# mmimplant.net
KiCad netlist of a schematic drawn in EAGLE
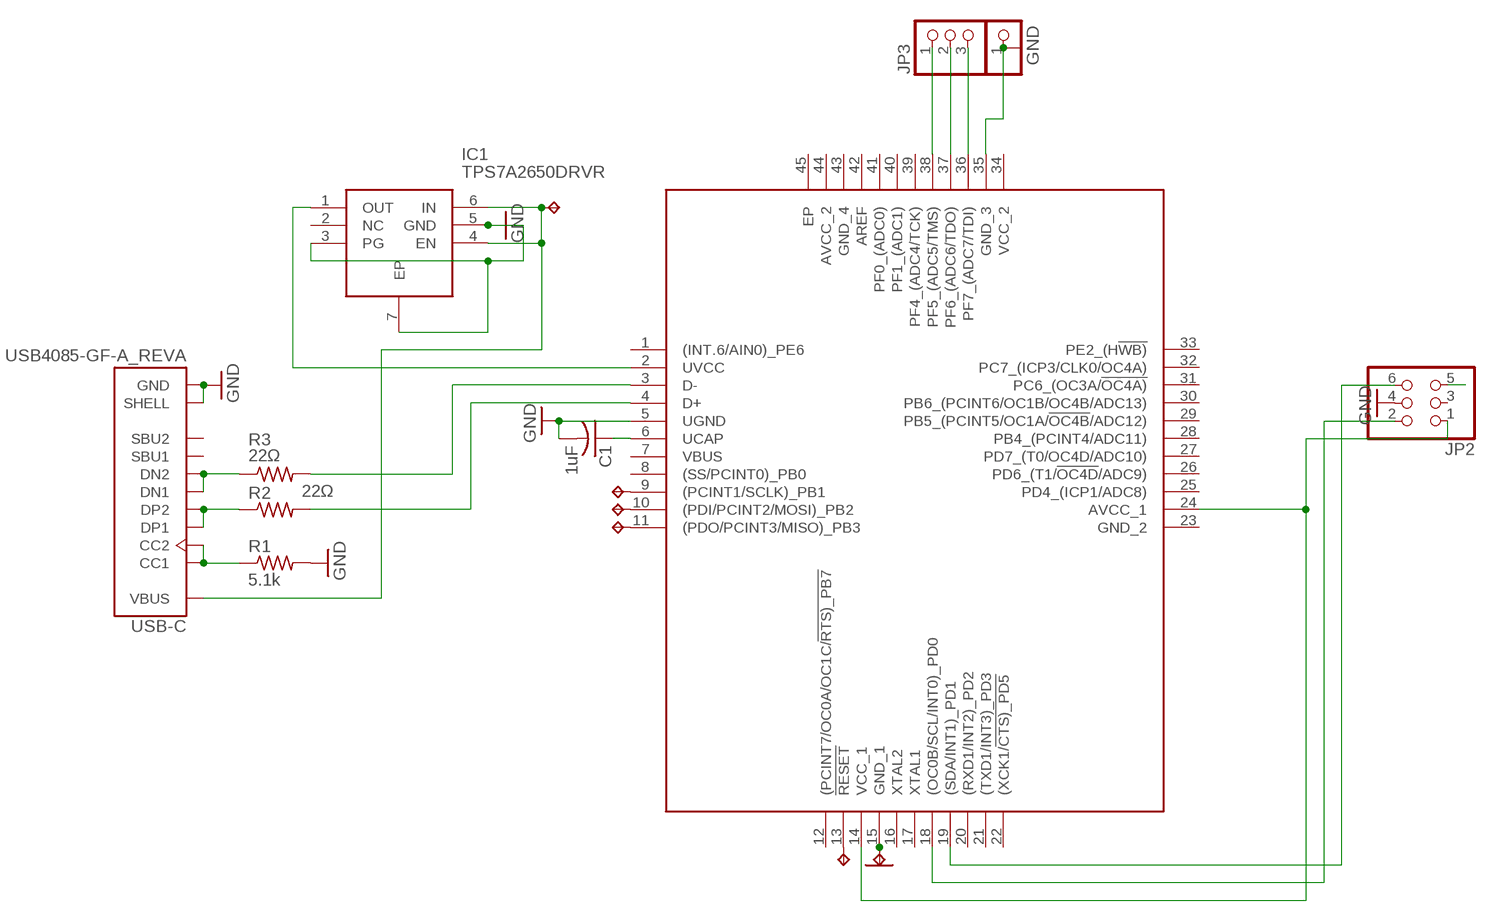
[diagram p0: schematic, sheet 1]

(export (version "E")
  (design (tool "Eeschema 10.0.6"))
  (components
    (comp (ref "5V")
      (value "TPTP17R")
      (footprint "eagle-import:TP17R")
      (libsource (lib "eagle-import") (part "TPTP17R"))
    )
    (comp (ref "C1")
      (value "1uF")
      (footprint "eagle-import:C0805")
      (libsource (lib "eagle-import") (part "C-USC0805"))
    )
    (comp (ref "GND")
      (value "TPTP17R")
      (footprint "eagle-import:TP17R")
      (libsource (lib "eagle-import") (part "TPTP17R"))
    )
    (comp (ref "IC1")
      (value "TPS7A2650DRVR")
      (footprint "eagle-import:SON65P200X200X80-7N")
      (fields (field (name "MOUSER_PART_NUMBER") "595-TPS7A2650DRVR"))
      (libsource (lib "eagle-import") (part "TPS7A2650DRVR"))
    )
    (comp (ref "IC2")
      (value "ATMEGA32U4-MU")
      (footprint "eagle-import:QFN50P700X700X100-45N")
      (fields (field (name "MOUSER_PART_NUMBER") "556-ATMEGA32U4-MU"))
      (libsource (lib "eagle-import") (part "ATMEGA32U4-MU"))
    )
    (comp (ref "JP1")
      (value "PINHD-1X1")
      (footprint "eagle-import:1X01")
      (libsource (lib "eagle-import") (part "PINHD-1X1"))
    )
    (comp (ref "JP2")
      (value "PINHD-2X3")
      (footprint "eagle-import:2X03")
      (libsource (lib "eagle-import") (part "PINHD-2X3"))
    )
    (comp (ref "JP3")
      (value "PINHD-1X3")
      (footprint "eagle-import:1X03")
      (libsource (lib "eagle-import") (part "PINHD-1X3"))
    )
    (comp (ref "MISO")
      (value "TPTP17R")
      (footprint "eagle-import:TP17R")
      (libsource (lib "eagle-import") (part "TPTP17R"))
    )
    (comp (ref "MOSI")
      (value "TPTP17R")
      (footprint "eagle-import:TP17R")
      (libsource (lib "eagle-import") (part "TPTP17R"))
    )
    (comp (ref "R1")
      (value "5.1k")
      (footprint "eagle-import:R0603")
      (libsource (lib "eagle-import") (part "R-US_R0603"))
    )
    (comp (ref "R2")
      (value "22Ω")
      (footprint "eagle-import:R0805")
      (libsource (lib "eagle-import") (part "R-US_R0805"))
    )
    (comp (ref "R3")
      (value "22Ω")
      (footprint "eagle-import:R0805")
      (libsource (lib "eagle-import") (part "R-US_R0805"))
    )
    (comp (ref "RST")
      (value "TPTP17R")
      (footprint "eagle-import:TP17R")
      (libsource (lib "eagle-import") (part "TPTP17R"))
    )
    (comp (ref "SCLK")
      (value "TPTP17R")
      (footprint "eagle-import:TP17R")
      (libsource (lib "eagle-import") (part "TPTP17R"))
    )
    (comp (ref "USB-C")
      (value "USB4085-GF-A_REVA")
      (footprint "eagle-import:GCT_USB4085-GF-A_REVA")
      (fields (field (name "MF") "Global Connector Technology") (field (name "MP") "USB4085-GF-A"))
      (libsource (lib "eagle-import") (part "USB4085-GF-A_REVA"))
    )
  )
  (nets
    (net (code "1") (name "GND") (class "Default")
      (node (ref "C1") (pin "2") (pinfunction "2_2") (pintype "passive"))
      (node (ref "GND") (pin "TP") (pinfunction "TP_TP") (pintype "input"))
      (node (ref "IC1") (pin "3") (pinfunction "PG_3") (pintype "bidirectional"))
      (node (ref "IC1") (pin "5") (pinfunction "GND_5") (pintype "bidirectional"))
      (node (ref "IC1") (pin "7") (pinfunction "EP_7") (pintype "bidirectional"))
      (node (ref "IC2") (pin "15") (pinfunction "GND_1_15") (pintype "bidirectional"))
      (node (ref "IC2") (pin "35") (pinfunction "GND_3_35") (pintype "bidirectional"))
      (node (ref "IC2") (pin "5") (pinfunction "UGND_5") (pintype "bidirectional"))
      (node (ref "JP1") (pin "1") (pinfunction "1_1") (pintype "passive"))
      (node (ref "JP2") (pin "4") (pinfunction "4_4") (pintype "passive"))
      (node (ref "R1") (pin "2") (pinfunction "2_2") (pintype "passive"))
      (node (ref "USB-C") (pin "A1") (pinfunction "GND_A1") (pintype "passive"))
      (node (ref "USB-C") (pin "A12") (pinfunction "GND_A12") (pintype "passive"))
      (node (ref "USB-C") (pin "B1") (pinfunction "GND_B1") (pintype "passive"))
      (node (ref "USB-C") (pin "B12") (pinfunction "GND_B12") (pintype "passive"))
      (node (ref "USB-C") (pin "P1") (pinfunction "SHELL_P1") (pintype "passive"))
      (node (ref "USB-C") (pin "P2") (pinfunction "SHELL_P2") (pintype "passive"))
      (node (ref "USB-C") (pin "P3") (pinfunction "SHELL_P3") (pintype "passive"))
      (node (ref "USB-C") (pin "P4") (pinfunction "SHELL_P4") (pintype "passive"))
    )
    (net (code "2") (name "Net-(IC1-EN)") (class "Default")
      (node (ref "5V") (pin "TP") (pinfunction "TP_TP") (pintype "input"))
      (node (ref "IC1") (pin "4") (pinfunction "EN_4") (pintype "bidirectional"))
      (node (ref "IC1") (pin "6") (pinfunction "IN_6") (pintype "bidirectional"))
      (node (ref "USB-C") (pin "A4") (pinfunction "VBUS_A4") (pintype "power_in"))
      (node (ref "USB-C") (pin "A9") (pinfunction "VBUS_A9") (pintype "power_in"))
      (node (ref "USB-C") (pin "B4") (pinfunction "VBUS_B4") (pintype "power_in"))
      (node (ref "USB-C") (pin "B9") (pinfunction "VBUS_B9") (pintype "power_in"))
    )
    (net (code "3") (name "Net-(IC1-OUT)") (class "Default")
      (node (ref "IC1") (pin "1") (pinfunction "OUT_1") (pintype "bidirectional"))
      (node (ref "IC2") (pin "2") (pinfunction "UVCC_2") (pintype "bidirectional"))
    )
    (net (code "4") (name "Net-(IC2-(OC0B{slash}SCL{slash}INT0)_PD0)") (class "Default")
      (node (ref "IC2") (pin "18") (pinfunction "(OC0B/SCL/INT0)_PD0_18") (pintype "bidirectional"))
      (node (ref "JP2") (pin "2") (pinfunction "2_2") (pintype "passive"))
    )
    (net (code "5") (name "Net-(IC2-(PCINT1{slash}SCLK)_PB1)") (class "Default")
      (node (ref "IC2") (pin "9") (pinfunction "(PCINT1/SCLK)_PB1_9") (pintype "bidirectional"))
      (node (ref "SCLK") (pin "TP") (pinfunction "TP_TP") (pintype "input"))
    )
    (net (code "6") (name "Net-(IC2-(PDI{slash}PCINT2{slash}MOSI)_PB2)") (class "Default")
      (node (ref "IC2") (pin "10") (pinfunction "(PDI/PCINT2/MOSI)_PB2_10") (pintype "bidirectional"))
      (node (ref "MOSI") (pin "TP") (pinfunction "TP_TP") (pintype "input"))
    )
    (net (code "7") (name "Net-(IC2-(PDO{slash}PCINT3{slash}MISO)_PB3)") (class "Default")
      (node (ref "IC2") (pin "11") (pinfunction "(PDO/PCINT3/MISO)_PB3_11") (pintype "bidirectional"))
      (node (ref "MISO") (pin "TP") (pinfunction "TP_TP") (pintype "input"))
    )
    (net (code "8") (name "Net-(IC2-(SDA{slash}INT1)_PD1)") (class "Default")
      (node (ref "IC2") (pin "19") (pinfunction "(SDA/INT1)_PD1_19") (pintype "bidirectional"))
      (node (ref "JP2") (pin "6") (pinfunction "6_6") (pintype "passive"))
    )
    (net (code "9") (name "Net-(IC2-AVCC_1)") (class "Default")
      (node (ref "IC2") (pin "14") (pinfunction "VCC_1_14") (pintype "bidirectional"))
      (node (ref "IC2") (pin "24") (pinfunction "AVCC_1_24") (pintype "bidirectional"))
      (node (ref "JP2") (pin "1") (pinfunction "1_1") (pintype "passive"))
    )
    (net (code "10") (name "Net-(IC2-D+)") (class "Default")
      (node (ref "IC2") (pin "4") (pinfunction "D+_4") (pintype "bidirectional"))
      (node (ref "R2") (pin "2") (pinfunction "2_2") (pintype "passive"))
    )
    (net (code "11") (name "Net-(IC2-D-)") (class "Default")
      (node (ref "IC2") (pin "3") (pinfunction "D-_3") (pintype "bidirectional"))
      (node (ref "R3") (pin "2") (pinfunction "2_2") (pintype "passive"))
    )
    (net (code "12") (name "Net-(IC2-PF5_(ADC5{slash}TMS))") (class "Default")
      (node (ref "IC2") (pin "38") (pinfunction "PF5_(ADC5/TMS)_38") (pintype "bidirectional"))
      (node (ref "JP3") (pin "1") (pinfunction "1_1") (pintype "passive"))
    )
    (net (code "13") (name "Net-(IC2-PF6_(ADC6{slash}TDO))") (class "Default")
      (node (ref "IC2") (pin "37") (pinfunction "PF6_(ADC6/TDO)_37") (pintype "bidirectional"))
      (node (ref "JP3") (pin "2") (pinfunction "2_2") (pintype "passive"))
    )
    (net (code "14") (name "Net-(IC2-PF7_(ADC7{slash}TDI))") (class "Default")
      (node (ref "IC2") (pin "36") (pinfunction "PF7_(ADC7/TDI)_36") (pintype "bidirectional"))
      (node (ref "JP3") (pin "3") (pinfunction "3_3") (pintype "passive"))
    )
    (net (code "15") (name "Net-(IC2-UCAP)") (class "Default")
      (node (ref "C1") (pin "1") (pinfunction "1_1") (pintype "passive"))
      (node (ref "IC2") (pin "6") (pinfunction "UCAP_6") (pintype "bidirectional"))
    )
    (net (code "16") (name "Net-(IC2-~{RESET})") (class "Default")
      (node (ref "IC2") (pin "13") (pinfunction "~{RESET}_13") (pintype "bidirectional"))
      (node (ref "RST") (pin "TP") (pinfunction "TP_TP") (pintype "input"))
    )
    (net (code "17") (name "Net-(USB-C-CC1)") (class "Default")
      (node (ref "R1") (pin "1") (pinfunction "1_1") (pintype "passive"))
      (node (ref "USB-C") (pin "A5") (pinfunction "CC1_A5") (pintype "bidirectional"))
      (node (ref "USB-C") (pin "B5") (pinfunction "CC2_B5") (pintype "bidirectional"))
    )
    (net (code "18") (name "Net-(USB-C-DN1)") (class "Default")
      (node (ref "R3") (pin "1") (pinfunction "1_1") (pintype "passive"))
      (node (ref "USB-C") (pin "A7") (pinfunction "DN1_A7") (pintype "bidirectional"))
      (node (ref "USB-C") (pin "B7") (pinfunction "DN2_B7") (pintype "bidirectional"))
    )
    (net (code "19") (name "Net-(USB-C-DP1)") (class "Default")
      (node (ref "R2") (pin "1") (pinfunction "1_1") (pintype "passive"))
      (node (ref "USB-C") (pin "A6") (pinfunction "DP1_A6") (pintype "bidirectional"))
      (node (ref "USB-C") (pin "B6") (pinfunction "DP2_B6") (pintype "bidirectional"))
    )
    (net (code "20") (name "unconnected-(IC1-NC-Pad2)") (class "Default")
      (node (ref "IC1") (pin "2") (pinfunction "NC_2") (pintype "no_connect"))
    )
    (net (code "21") (name "unconnected-(IC2-(INT.6{slash}AIN0)_PE6-Pad1)") (class "Default")
      (node (ref "IC2") (pin "1") (pinfunction "(INT.6/AIN0)_PE6_1") (pintype "bidirectional"))
    )
    (net (code "22") (name "unconnected-(IC2-(PCINT7{slash}OC0A{slash}OC1C{slash}~{RTS})_PB7-Pad12)") (class "Default")
      (node (ref "IC2") (pin "12") (pinfunction "(PCINT7/OC0A/OC1C/~{RTS})_PB7_12") (pintype "bidirectional"))
    )
    (net (code "23") (name "unconnected-(IC2-(RXD1{slash}INT2)_PD2-Pad20)") (class "Default")
      (node (ref "IC2") (pin "20") (pinfunction "(RXD1/INT2)_PD2_20") (pintype "bidirectional"))
    )
    (net (code "24") (name "unconnected-(IC2-(SS{slash}PCINT0)_PB0-Pad8)") (class "Default")
      (node (ref "IC2") (pin "8") (pinfunction "(SS/PCINT0)_PB0_8") (pintype "bidirectional"))
    )
    (net (code "25") (name "unconnected-(IC2-(TXD1{slash}INT3)_PD3-Pad21)") (class "Default")
      (node (ref "IC2") (pin "21") (pinfunction "(TXD1/INT3)_PD3_21") (pintype "bidirectional"))
    )
    (net (code "26") (name "unconnected-(IC2-(XCK1{slash}~{CTS})_PD5-Pad22)") (class "Default")
      (node (ref "IC2") (pin "22") (pinfunction "(XCK1/~{CTS})_PD5_22") (pintype "bidirectional"))
    )
    (net (code "27") (name "unconnected-(IC2-AREF-Pad42)") (class "Default")
      (node (ref "IC2") (pin "42") (pinfunction "AREF_42") (pintype "bidirectional"))
    )
    (net (code "28") (name "unconnected-(IC2-AVCC_2-Pad44)") (class "Default")
      (node (ref "IC2") (pin "44") (pinfunction "AVCC_2_44") (pintype "bidirectional"))
    )
    (net (code "29") (name "unconnected-(IC2-EP-Pad45)") (class "Default")
      (node (ref "IC2") (pin "45") (pinfunction "EP_45") (pintype "bidirectional"))
    )
    (net (code "30") (name "unconnected-(IC2-GND_2-Pad23)") (class "Default")
      (node (ref "IC2") (pin "23") (pinfunction "GND_2_23") (pintype "bidirectional"))
    )
    (net (code "31") (name "unconnected-(IC2-GND_4-Pad43)") (class "Default")
      (node (ref "IC2") (pin "43") (pinfunction "GND_4_43") (pintype "bidirectional"))
    )
    (net (code "32") (name "unconnected-(IC2-PB4_(PCINT4{slash}ADC11)-Pad28)") (class "Default")
      (node (ref "IC2") (pin "28") (pinfunction "PB4_(PCINT4/ADC11)_28") (pintype "bidirectional"))
    )
    (net (code "33") (name "unconnected-(IC2-PB5_(PCINT5{slash}OC1A{slash}~{OC4B}{slash}ADC12)-Pad29)") (class "Default")
      (node (ref "IC2") (pin "29") (pinfunction "PB5_(PCINT5/OC1A/~{OC4B}/ADC12)_29") (pintype "bidirectional"))
    )
    (net (code "34") (name "unconnected-(IC2-PB6_(PCINT6{slash}OC1B{slash}OC4B{slash}ADC13)-Pad30)") (class "Default")
      (node (ref "IC2") (pin "30") (pinfunction "PB6_(PCINT6/OC1B/OC4B/ADC13)_30") (pintype "bidirectional"))
    )
    (net (code "35") (name "unconnected-(IC2-PC6_(OC3A{slash}~{OC4A})-Pad31)") (class "Default")
      (node (ref "IC2") (pin "31") (pinfunction "PC6_(OC3A/~{OC4A})_31") (pintype "bidirectional"))
    )
    (net (code "36") (name "unconnected-(IC2-PC7_(ICP3{slash}CLK0{slash}OC4A)-Pad32)") (class "Default")
      (node (ref "IC2") (pin "32") (pinfunction "PC7_(ICP3/CLK0/OC4A)_32") (pintype "bidirectional"))
    )
    (net (code "37") (name "unconnected-(IC2-PD4_(ICP1{slash}ADC8)-Pad25)") (class "Default")
      (node (ref "IC2") (pin "25") (pinfunction "PD4_(ICP1/ADC8)_25") (pintype "bidirectional"))
    )
    (net (code "38") (name "unconnected-(IC2-PD6_(T1{slash}~{OC4D}{slash}ADC9)-Pad26)") (class "Default")
      (node (ref "IC2") (pin "26") (pinfunction "PD6_(T1/~{OC4D}/ADC9)_26") (pintype "bidirectional"))
    )
    (net (code "39") (name "unconnected-(IC2-PD7_(T0{slash}OC4D{slash}ADC10)-Pad27)") (class "Default")
      (node (ref "IC2") (pin "27") (pinfunction "PD7_(T0/OC4D/ADC10)_27") (pintype "bidirectional"))
    )
    (net (code "40") (name "unconnected-(IC2-PE2_(H~{WB})-Pad33)") (class "Default")
      (node (ref "IC2") (pin "33") (pinfunction "PE2_(H~{WB})_33") (pintype "bidirectional"))
    )
    (net (code "41") (name "unconnected-(IC2-PF0_(ADC0)-Pad41)") (class "Default")
      (node (ref "IC2") (pin "41") (pinfunction "PF0_(ADC0)_41") (pintype "bidirectional"))
    )
    (net (code "42") (name "unconnected-(IC2-PF1_(ADC1)-Pad40)") (class "Default")
      (node (ref "IC2") (pin "40") (pinfunction "PF1_(ADC1)_40") (pintype "bidirectional"))
    )
    (net (code "43") (name "unconnected-(IC2-PF4_(ADC4{slash}TCK)-Pad39)") (class "Default")
      (node (ref "IC2") (pin "39") (pinfunction "PF4_(ADC4/TCK)_39") (pintype "bidirectional"))
    )
    (net (code "44") (name "unconnected-(IC2-VBUS-Pad7)") (class "Default")
      (node (ref "IC2") (pin "7") (pinfunction "VBUS_7") (pintype "bidirectional"))
    )
    (net (code "45") (name "unconnected-(IC2-VCC_2-Pad34)") (class "Default")
      (node (ref "IC2") (pin "34") (pinfunction "VCC_2_34") (pintype "bidirectional"))
    )
    (net (code "46") (name "unconnected-(IC2-XTAL1-Pad17)") (class "Default")
      (node (ref "IC2") (pin "17") (pinfunction "XTAL1_17") (pintype "bidirectional"))
    )
    (net (code "47") (name "unconnected-(IC2-XTAL2-Pad16)") (class "Default")
      (node (ref "IC2") (pin "16") (pinfunction "XTAL2_16") (pintype "bidirectional"))
    )
    (net (code "48") (name "unconnected-(JP2-Pad3)") (class "Default")
      (node (ref "JP2") (pin "3") (pinfunction "3_3") (pintype "passive"))
    )
    (net (code "49") (name "unconnected-(JP2-Pad5)") (class "Default")
      (node (ref "JP2") (pin "5") (pinfunction "5_5") (pintype "passive"))
    )
    (net (code "50") (name "unconnected-(USB-C-SBU1-PadA8)") (class "Default")
      (node (ref "USB-C") (pin "A8") (pinfunction "SBU1_A8") (pintype "bidirectional"))
    )
    (net (code "51") (name "unconnected-(USB-C-SBU2-PadB8)") (class "Default")
      (node (ref "USB-C") (pin "B8") (pinfunction "SBU2_B8") (pintype "bidirectional"))
    )
  )
)
